# Buzzer-Schematic.net
KiCad netlist of a schematic drawn in Altium Designer
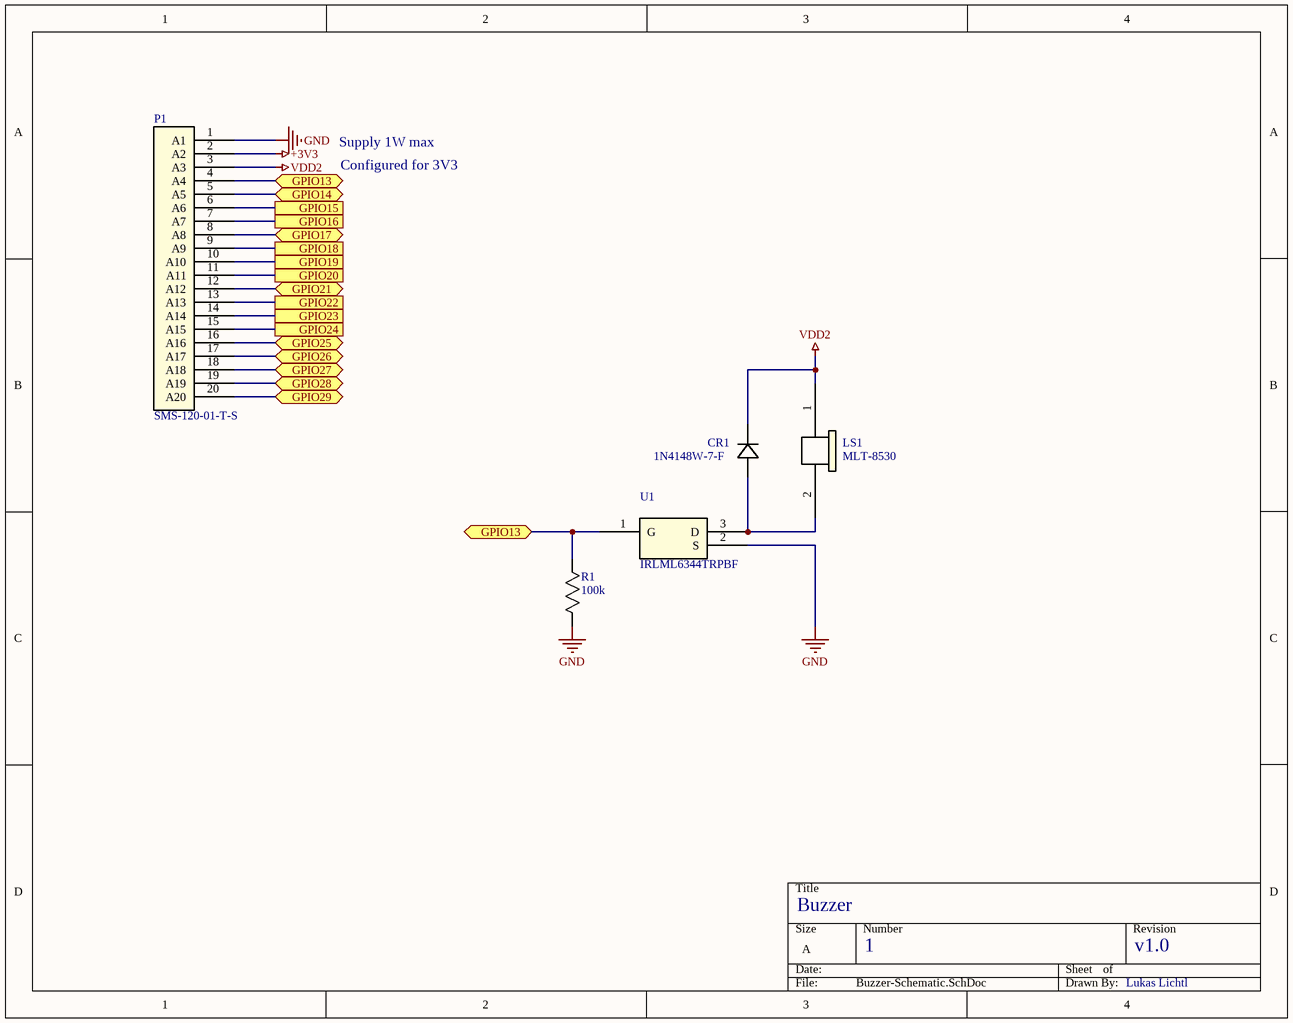
[diagram p0: Buzzer-Schematic.SchDoc]

(export (version "E")
  (design (tool "Eeschema 10.0.6"))
  (components
    (comp (ref "CR1")
      (value "1N4148W-7-F")
      (footprint "SOD123_DIO")
      (description "No Description Available")
      (libsource (lib "1N4148W-7-F") (part "1N4148W-7-F"))
    )
    (comp (ref "LS1")
      (value "MLT-8530")
      (footprint "MLT-8530_JHE")
      (description "No Description Available")
      (libsource (lib "MLT-8530") (part "MLT-8530"))
    )
    (comp (ref "P1")
      (value "SMS-120-01-T-S")
      (footprint "SMS-S-120")
      (description "No Description Available")
      (libsource (lib "SMS-120-01-T-S") (part "SMS-120-01-T-S"))
    )
    (comp (ref "R1")
      (value "100k")
      (footprint "RC0603N_YAG")
      (description "No Description Available")
      (libsource (lib "RC0603FR-07470RL") (part "RC0603FR-07470RL"))
    )
    (comp (ref "U1")
      (value "IRLML6344TRPBF")
      (footprint "IRLML6344TRPBF_INF")
      (description "No Description Available")
      (libsource (lib "IRLML6344TRPBF") (part "IRLML6344TRPBF"))
    )
  )
  (nets
    (net (code "1") (name "+3V3") (class "Default")
      (node (ref "P1") (pin "2") (pinfunction "A2_2") (pintype "passive"))
    )
    (net (code "2") (name "/GPIO13") (class "Default")
      (node (ref "P1") (pin "4") (pinfunction "A4_4") (pintype "passive"))
      (node (ref "R1") (pin "2") (pinfunction "2_2") (pintype "passive"))
      (node (ref "U1") (pin "1") (pinfunction "G_1") (pintype "passive"))
    )
    (net (code "3") (name "/GPIO14") (class "Default")
      (node (ref "P1") (pin "5") (pinfunction "A5_5") (pintype "passive"))
    )
    (net (code "4") (name "/GPIO15") (class "Default")
      (node (ref "P1") (pin "6") (pinfunction "A6_6") (pintype "passive"))
    )
    (net (code "5") (name "/GPIO16") (class "Default")
      (node (ref "P1") (pin "7") (pinfunction "A7_7") (pintype "passive"))
    )
    (net (code "6") (name "/GPIO17") (class "Default")
      (node (ref "P1") (pin "8") (pinfunction "A8_8") (pintype "passive"))
    )
    (net (code "7") (name "/GPIO18") (class "Default")
      (node (ref "P1") (pin "9") (pinfunction "A9_9") (pintype "passive"))
    )
    (net (code "8") (name "/GPIO19") (class "Default")
      (node (ref "P1") (pin "10") (pinfunction "A10_10") (pintype "passive"))
    )
    (net (code "9") (name "/GPIO20") (class "Default")
      (node (ref "P1") (pin "11") (pinfunction "A11_11") (pintype "passive"))
    )
    (net (code "10") (name "/GPIO21") (class "Default")
      (node (ref "P1") (pin "12") (pinfunction "A12_12") (pintype "passive"))
    )
    (net (code "11") (name "/GPIO22") (class "Default")
      (node (ref "P1") (pin "13") (pinfunction "A13_13") (pintype "passive"))
    )
    (net (code "12") (name "/GPIO23") (class "Default")
      (node (ref "P1") (pin "14") (pinfunction "A14_14") (pintype "passive"))
    )
    (net (code "13") (name "/GPIO24") (class "Default")
      (node (ref "P1") (pin "15") (pinfunction "A15_15") (pintype "passive"))
    )
    (net (code "14") (name "/GPIO25") (class "Default")
      (node (ref "P1") (pin "16") (pinfunction "A16_16") (pintype "passive"))
    )
    (net (code "15") (name "/GPIO26") (class "Default")
      (node (ref "P1") (pin "17") (pinfunction "A17_17") (pintype "passive"))
    )
    (net (code "16") (name "/GPIO27") (class "Default")
      (node (ref "P1") (pin "18") (pinfunction "A18_18") (pintype "passive"))
    )
    (net (code "17") (name "/GPIO28") (class "Default")
      (node (ref "P1") (pin "19") (pinfunction "A19_19") (pintype "passive"))
    )
    (net (code "18") (name "/GPIO29") (class "Default")
      (node (ref "P1") (pin "20") (pinfunction "A20_20") (pintype "passive"))
    )
    (net (code "19") (name "GND") (class "Default")
      (node (ref "P1") (pin "1") (pinfunction "A1_1") (pintype "passive"))
      (node (ref "R1") (pin "1") (pinfunction "1_1") (pintype "passive"))
      (node (ref "U1") (pin "2") (pinfunction "S_2") (pintype "passive"))
    )
    (net (code "20") (name "Net-(U1-D)") (class "Default")
      (node (ref "CR1") (pin "2") (pinfunction "2_2") (pintype "passive"))
      (node (ref "LS1") (pin "2") (pinfunction "2_2") (pintype "passive"))
      (node (ref "U1") (pin "3") (pinfunction "D_3") (pintype "passive"))
    )
    (net (code "21") (name "VDD2") (class "Default")
      (node (ref "CR1") (pin "1") (pinfunction "1_1") (pintype "passive"))
      (node (ref "LS1") (pin "1") (pinfunction "1_1") (pintype "passive"))
      (node (ref "P1") (pin "3") (pinfunction "A3_3") (pintype "passive"))
    )
  )
)
